# 534_Botones.net
KiCad netlist of a schematic drawn in Altium Designer
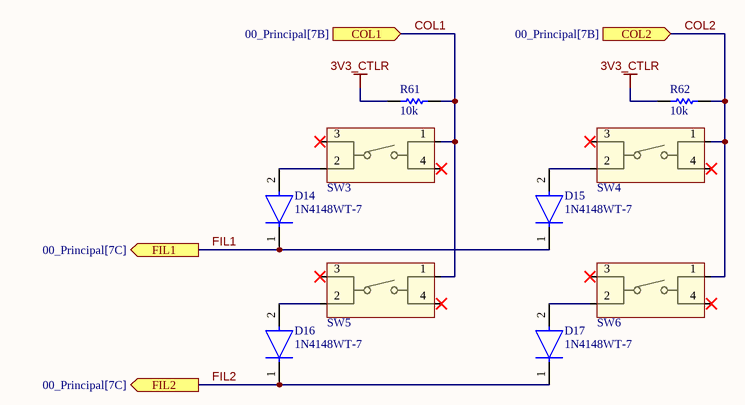
[diagram p0: 534_Botones.SchDoc]

(export (version "E")
  (design (tool "Eeschema 10.0.6"))
  (components
    (comp (ref "D14")
      (value "1N4148WT-7")
      (footprint "FP-SOD523-MFG")
      (description "DIODE GEN PURP 80V 125MA SOD523")
      (libsource (lib "Altium Content Vault") (part "d7152d700b627762746794eb795d46e"))
    )
    (comp (ref "D15")
      (value "1N4148WT-7")
      (footprint "FP-SOD523-MFG")
      (description "DIODE GEN PURP 80V 125MA SOD523")
      (libsource (lib "Altium Content Vault") (part "d7152d700b627762746794eb795d46e"))
    )
    (comp (ref "D16")
      (value "1N4148WT-7")
      (footprint "FP-SOD523-MFG")
      (description "DIODE GEN PURP 80V 125MA SOD523")
      (libsource (lib "Altium Content Vault") (part "d7152d700b627762746794eb795d46e"))
    )
    (comp (ref "D17")
      (value "1N4148WT-7")
      (footprint "FP-SOD523-MFG")
      (description "DIODE GEN PURP 80V 125MA SOD523")
      (libsource (lib "Altium Content Vault") (part "d7152d700b627762746794eb795d46e"))
    )
    (comp (ref "R61")
      (value "10k")
      (footprint "RESC1005X40X25ML05T05")
      (fields (field (name "MANUFACTURER") "Panasonic") (field (name "PART NUMBER") "ERJ-2RHD1002X"))
      (libsource (lib "Altium Content Vault") (part "RES"))
    )
    (comp (ref "R62")
      (value "10k")
      (footprint "RESC1005X40X25ML05T05")
      (fields (field (name "MANUFACTURER") "Panasonic") (field (name "PART NUMBER") "ERJ-2RHD1002X"))
      (libsource (lib "Altium Content Vault") (part "RES"))
    )
    (comp (ref "SW3")
      (value "KSC441G70SHLFSPF")
      (footprint "KSC441G 70SH LFS PF")
      (description "Switch Tactile N.O. SPST Button 1VA 32VDC 50mA 4N Gull Wing SMD T/R")
      (fields (field (name "MANUFACTURER") "C&K Components"))
      (libsource (lib "Esquemas") (part "KSC441G70SHLFSPF"))
    )
    (comp (ref "SW4")
      (value "KSC441G70SHLFSPF")
      (footprint "KSC441G 70SH LFS PF")
      (description "Switch Tactile N.O. SPST Button 1VA 32VDC 50mA 4N Gull Wing SMD T/R")
      (fields (field (name "MANUFACTURER") "C&K Components"))
      (libsource (lib "Esquemas") (part "KSC441G70SHLFSPF"))
    )
    (comp (ref "SW5")
      (value "KSC441G70SHLFSPF")
      (footprint "KSC441G 70SH LFS PF")
      (description "Switch Tactile N.O. SPST Button 1VA 32VDC 50mA 4N Gull Wing SMD T/R")
      (fields (field (name "MANUFACTURER") "C&K Components"))
      (libsource (lib "Esquemas") (part "KSC441G70SHLFSPF"))
    )
    (comp (ref "SW6")
      (value "KSC441G70SHLFSPF")
      (footprint "KSC441G 70SH LFS PF")
      (description "Switch Tactile N.O. SPST Button 1VA 32VDC 50mA 4N Gull Wing SMD T/R")
      (fields (field (name "MANUFACTURER") "C&K Components"))
      (libsource (lib "Esquemas") (part "KSC441G70SHLFSPF"))
    )
  )
  (nets
    (net (code "1") (name "/COL1") (class "Default")
      (node (ref "R61") (pin "1") (pinfunction "1_1") (pintype "passive"))
      (node (ref "SW3") (pin "1") (pinfunction "0_1") (pintype "passive"))
      (node (ref "SW5") (pin "1") (pinfunction "0_1") (pintype "passive"))
    )
    (net (code "2") (name "/COL2") (class "Default")
      (node (ref "R62") (pin "1") (pinfunction "1_1") (pintype "passive"))
      (node (ref "SW4") (pin "1") (pinfunction "0_1") (pintype "passive"))
      (node (ref "SW6") (pin "1") (pinfunction "0_1") (pintype "passive"))
    )
    (net (code "3") (name "/FIL1") (class "Default")
      (node (ref "D14") (pin "1") (pinfunction "C_1") (pintype "passive"))
      (node (ref "D15") (pin "1") (pinfunction "C_1") (pintype "passive"))
    )
    (net (code "4") (name "/FIL2") (class "Default")
      (node (ref "D16") (pin "1") (pinfunction "C_1") (pintype "passive"))
      (node (ref "D17") (pin "1") (pinfunction "C_1") (pintype "passive"))
    )
    (net (code "5") (name "3V3_CTLR") (class "Default")
      (node (ref "R61") (pin "2") (pinfunction "2_2") (pintype "passive"))
      (node (ref "R62") (pin "2") (pinfunction "2_2") (pintype "passive"))
    )
    (net (code "6") (name "Net-(D14-A)") (class "Default")
      (node (ref "D14") (pin "2") (pinfunction "A_2") (pintype "passive"))
      (node (ref "SW3") (pin "2") (pinfunction "1_2") (pintype "passive"))
    )
    (net (code "7") (name "Net-(D15-A)") (class "Default")
      (node (ref "D15") (pin "2") (pinfunction "A_2") (pintype "passive"))
      (node (ref "SW4") (pin "2") (pinfunction "1_2") (pintype "passive"))
    )
    (net (code "8") (name "Net-(D16-A)") (class "Default")
      (node (ref "D16") (pin "2") (pinfunction "A_2") (pintype "passive"))
      (node (ref "SW5") (pin "2") (pinfunction "1_2") (pintype "passive"))
    )
    (net (code "9") (name "Net-(D17-A)") (class "Default")
      (node (ref "D17") (pin "2") (pinfunction "A_2") (pintype "passive"))
      (node (ref "SW6") (pin "2") (pinfunction "1_2") (pintype "passive"))
    )
    (net (code "10") (name "unconnected-(SW3-2-Pad3)") (class "Default")
      (node (ref "SW3") (pin "3") (pinfunction "2_3") (pintype "passive+no_connect"))
    )
    (net (code "11") (name "unconnected-(SW3-3-Pad4)") (class "Default")
      (node (ref "SW3") (pin "4") (pinfunction "3_4") (pintype "passive+no_connect"))
    )
    (net (code "12") (name "unconnected-(SW4-2-Pad3)") (class "Default")
      (node (ref "SW4") (pin "3") (pinfunction "2_3") (pintype "passive+no_connect"))
    )
    (net (code "13") (name "unconnected-(SW4-3-Pad4)") (class "Default")
      (node (ref "SW4") (pin "4") (pinfunction "3_4") (pintype "passive+no_connect"))
    )
    (net (code "14") (name "unconnected-(SW5-2-Pad3)") (class "Default")
      (node (ref "SW5") (pin "3") (pinfunction "2_3") (pintype "passive+no_connect"))
    )
    (net (code "15") (name "unconnected-(SW5-3-Pad4)") (class "Default")
      (node (ref "SW5") (pin "4") (pinfunction "3_4") (pintype "passive+no_connect"))
    )
    (net (code "16") (name "unconnected-(SW6-2-Pad3)") (class "Default")
      (node (ref "SW6") (pin "3") (pinfunction "2_3") (pintype "passive+no_connect"))
    )
    (net (code "17") (name "unconnected-(SW6-3-Pad4)") (class "Default")
      (node (ref "SW6") (pin "4") (pinfunction "3_4") (pintype "passive+no_connect"))
    )
  )
)
